# NRF8001_BLE_COMMS.net
KiCad netlist of a schematic drawn in EAGLE
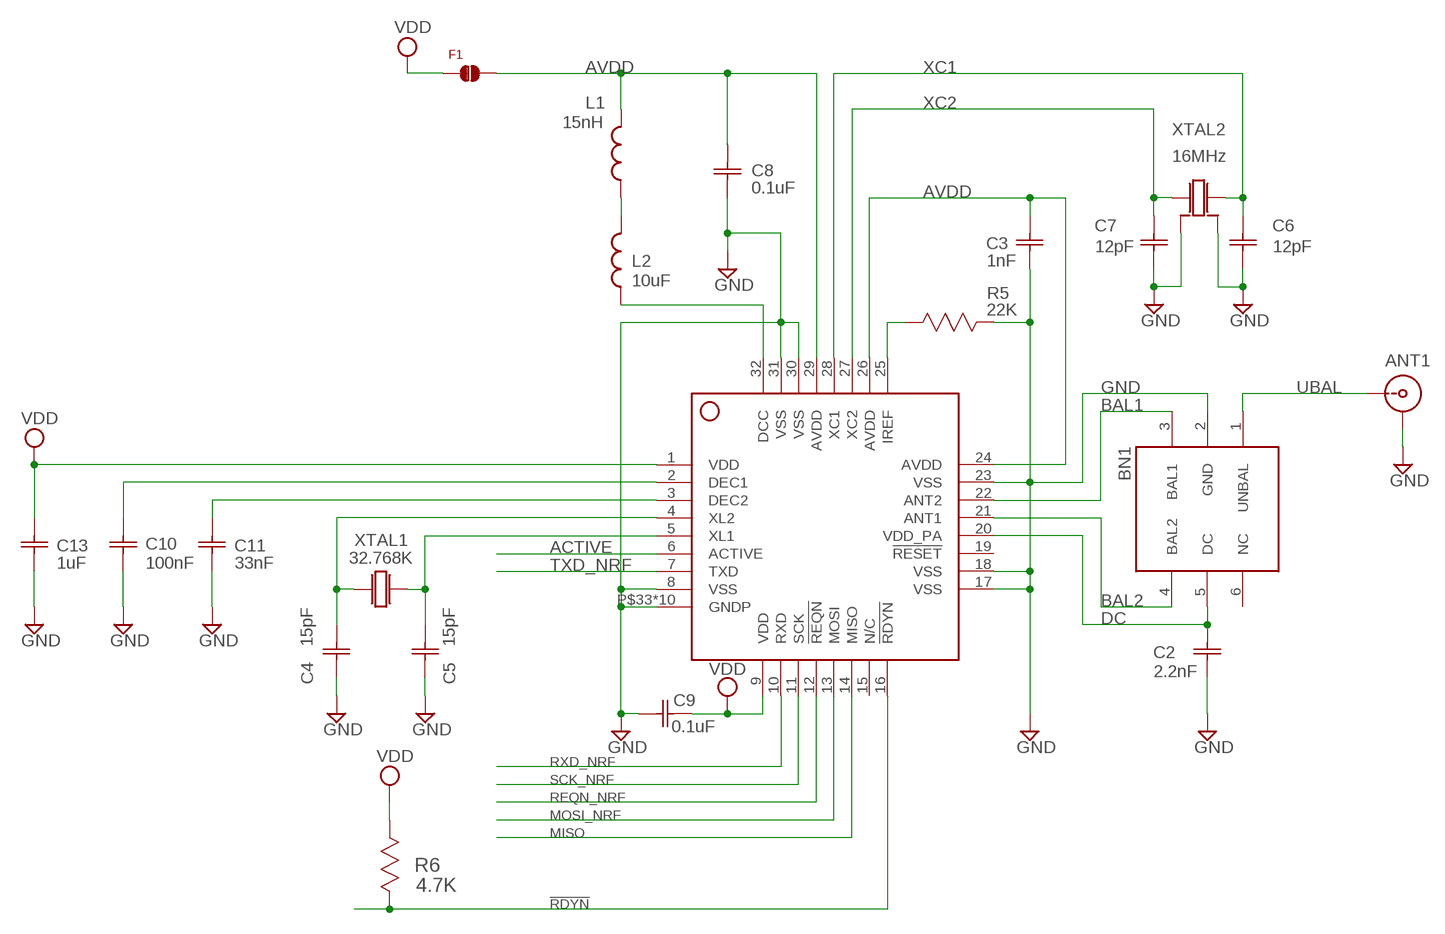
[diagram p0: schematic, sheet 1]

(export (version "E")
  (design (tool "Eeschema 10.0.6"))
  (components
    (comp (ref "ANT1")
      (value "U.FL-R-SMT(01)")
      (footprint "eagle-import:U.FL")
      (fields (field (name "MANUFACTURER") "HIROSE"))
      (libsource (lib "eagle-import") (part "U.FL-R-SMT(01)"))
    )
    (comp (ref "BN1")
      (value "2450BM14A0002")
      (footprint "eagle-import:BALUN")
      (fields (field (name "MANUFACTURER") "JOHANSON"))
      (libsource (lib "eagle-import") (part "2450BM14A0002"))
    )
    (comp (ref "C2")
      (value "2.2nF")
      (footprint "eagle-import:CAPC1608X85N")
      (fields (field (name "MPN") "C0603C222K5RACTU") (field (name "TOLERANCE") "±10%"))
      (libsource (lib "eagle-import") (part "C0603C222K5RACTU"))
    )
    (comp (ref "C3")
      (value "1nF")
      (footprint "eagle-import:CAPC1608X85N")
      (fields (field (name "MPN") "C0603C102J5GACTU") (field (name "TOLERANCE") "±5%"))
      (libsource (lib "eagle-import") (part "C0603C102J5GACTU"))
    )
    (comp (ref "C4")
      (value "15pF")
      (footprint "eagle-import:CAPC1608X85N")
      (fields (field (name "MPN") "C0603C150J5GACTU") (field (name "TOLERANCE") "±5%"))
      (libsource (lib "eagle-import") (part "C0603C150J5GACTU"))
    )
    (comp (ref "C5")
      (value "15pF")
      (footprint "eagle-import:CAPC1608X85N")
      (fields (field (name "MPN") "C0603C150J5GACTU") (field (name "TOLERANCE") "±5%"))
      (libsource (lib "eagle-import") (part "C0603C150J5GACTU"))
    )
    (comp (ref "C6")
      (value "12pF")
      (footprint "eagle-import:CAPC1608X85N")
      (fields (field (name "MPN") "C0603C120J5GACTU") (field (name "TOLERANCE") "±5%"))
      (libsource (lib "eagle-import") (part "C0603C120J5GACTU"))
    )
    (comp (ref "C7")
      (value "12pF")
      (footprint "eagle-import:CAPC1608X85N")
      (fields (field (name "MPN") "C0603C120J5GACTU") (field (name "TOLERANCE") "±5%"))
      (libsource (lib "eagle-import") (part "C0603C120J5GACTU"))
    )
    (comp (ref "C8")
      (value "0.1uF")
      (footprint "eagle-import:CAPC1608X90N")
      (fields (field (name "MPN") "0603YC104K4T4A") (field (name "TOLERANCE") "±10%"))
      (libsource (lib "eagle-import") (part "0603YC104K4T4A"))
    )
    (comp (ref "C9")
      (value "0.1uF")
      (footprint "eagle-import:CAPC1608X90N")
      (fields (field (name "MPN") "0603YC104K4T4A") (field (name "TOLERANCE") "±10%"))
      (libsource (lib "eagle-import") (part "0603YC104K4T4A"))
    )
    (comp (ref "C10")
      (value "100nF")
      (footprint "eagle-import:CAPC1608X90N")
      (fields (field (name "MPN") "06033C104JAT2A") (field (name "TOLERANCE") "±5%"))
      (libsource (lib "eagle-import") (part "06033C104JAT2A"))
    )
    (comp (ref "C11")
      (value "33nF")
      (footprint "eagle-import:CAPC1608X85N")
      (fields (field (name "MPN") "C0603C333K5RACTU") (field (name "TOLERANCE") "±10%"))
      (libsource (lib "eagle-import") (part "C0603C333K5RACTU"))
    )
    (comp (ref "C13")
      (value "1uF")
      (footprint "eagle-import:CAPC1608X90N")
      (fields (field (name "MPN") "0603YD105MAT4A") (field (name "TOLERANCE") "±20%"))
      (libsource (lib "eagle-import") (part "0603YD105MAT4A"))
    )
    (comp (ref "F1")
      (value "MMZ1608B121C")
      (footprint "eagle-import:0603")
      (libsource (lib "eagle-import") (part "MMZ1608B121C"))
    )
    (comp (ref "L1")
      (value "15nH")
      (footprint "eagle-import:0402")
      (libsource (lib "eagle-import") (part "HK100515NJ-T"))
    )
    (comp (ref "L2")
      (value "10uF")
      (footprint "eagle-import:0603")
      (libsource (lib "eagle-import") (part "LBMF1608T100K"))
    )
    (comp (ref "R5")
      (value "22K")
      (footprint "eagle-import:RESC1608X60N")
      (fields (field (name "MPN") "MC0.063W06031%22K") (field (name "TOLERANCE") "±1%"))
      (libsource (lib "eagle-import") (part "MC0.063W06031%22K"))
    )
    (comp (ref "R6")
      (value "4.7K")
      (footprint "eagle-import:RESC1608X60N")
      (fields (field (name "MPN") "MC0.063W06031%4K7") (field (name "TOLERANCE") "1%"))
      (libsource (lib "eagle-import") (part "MC0.063W06031%4K7"))
    )
    (comp (ref "U2")
      (value "NRF8001")
      (footprint "eagle-import:QFN50P500X500X90-33N")
      (fields (field (name "MANUFACTURER") "NORDIC SEMICONDUCTOR") (field (name "PARTNO") "nRF8001"))
      (libsource (lib "eagle-import") (part "NRF8001"))
    )
    (comp (ref "XTAL1")
      (value "32.768K")
      (footprint "eagle-import:3215")
      (libsource (lib "eagle-import") (part "NX3215SA-32.768K-STD-MUA-9"))
    )
    (comp (ref "XTAL2")
      (value "16MHz")
      (footprint "eagle-import:3225")
      (libsource (lib "eagle-import") (part "TSX-3225-16.0000MF18X-AC3"))
    )
  )
  (nets
    (net (code "1") (name "/ACTIVE") (class "Default")
      (node (ref "U2") (pin "6") (pinfunction "ACTIVE_6") (pintype "bidirectional"))
    )
    (net (code "2") (name "/AVDD") (class "Default")
      (node (ref "C3") (pin "2") (pinfunction "C2_2") (pintype "passive"))
      (node (ref "C8") (pin "2") (pinfunction "C2_2") (pintype "passive"))
      (node (ref "F1") (pin "P$2") (pinfunction "2_P$2") (pintype "bidirectional"))
      (node (ref "L1") (pin "P$2") (pinfunction "P$2_P$2") (pintype "bidirectional"))
      (node (ref "U2") (pin "24") (pinfunction "AVDD_24") (pintype "bidirectional"))
      (node (ref "U2") (pin "26") (pinfunction "AVDD_26") (pintype "bidirectional"))
      (node (ref "U2") (pin "29") (pinfunction "AVDD_29") (pintype "bidirectional"))
    )
    (net (code "3") (name "/BAL1") (class "Default")
      (node (ref "BN1") (pin "3") (pinfunction "BAL1_3") (pintype "bidirectional"))
      (node (ref "U2") (pin "22") (pinfunction "ANT2_22") (pintype "bidirectional"))
    )
    (net (code "4") (name "/BAL2") (class "Default")
      (node (ref "BN1") (pin "4") (pinfunction "BAL2_4") (pintype "bidirectional"))
      (node (ref "U2") (pin "21") (pinfunction "ANT1_21") (pintype "bidirectional"))
    )
    (net (code "5") (name "/DC") (class "Default")
      (node (ref "BN1") (pin "5") (pinfunction "DC_5") (pintype "bidirectional"))
      (node (ref "C2") (pin "2") (pinfunction "C2_2") (pintype "passive"))
      (node (ref "U2") (pin "20") (pinfunction "VDD_PA_20") (pintype "bidirectional"))
    )
    (net (code "6") (name "/MISO") (class "Default")
      (node (ref "U2") (pin "14") (pinfunction "MISO_14") (pintype "bidirectional"))
    )
    (net (code "7") (name "/MOSI_NRF") (class "Default")
      (node (ref "U2") (pin "13") (pinfunction "MOSI_13") (pintype "bidirectional"))
    )
    (net (code "8") (name "/REQN_NRF") (class "Default")
      (node (ref "U2") (pin "12") (pinfunction "~{REQN}_12") (pintype "bidirectional"))
    )
    (net (code "9") (name "/RXD_NRF") (class "Default")
      (node (ref "U2") (pin "10") (pinfunction "RXD_10") (pintype "bidirectional"))
    )
    (net (code "10") (name "/SCK_NRF") (class "Default")
      (node (ref "U2") (pin "11") (pinfunction "SCK_11") (pintype "bidirectional"))
    )
    (net (code "11") (name "/TXD_NRF") (class "Default")
      (node (ref "U2") (pin "7") (pinfunction "TXD_7") (pintype "bidirectional"))
    )
    (net (code "12") (name "/UBAL") (class "Default")
      (node (ref "ANT1") (pin "1") (pinfunction "P$1_1") (pintype "bidirectional"))
      (node (ref "BN1") (pin "1") (pinfunction "UNBAL_1") (pintype "bidirectional"))
    )
    (net (code "13") (name "/XC1") (class "Default")
      (node (ref "C6") (pin "2") (pinfunction "C2_2") (pintype "passive"))
      (node (ref "U2") (pin "28") (pinfunction "XC1_28") (pintype "bidirectional"))
      (node (ref "XTAL2") (pin "3") (pinfunction "3_3") (pintype "bidirectional"))
    )
    (net (code "14") (name "/XC2") (class "Default")
      (node (ref "C7") (pin "2") (pinfunction "C2_2") (pintype "passive"))
      (node (ref "U2") (pin "27") (pinfunction "XC2_27") (pintype "bidirectional"))
      (node (ref "XTAL2") (pin "1") (pinfunction "1_1") (pintype "bidirectional"))
    )
    (net (code "15") (name "/~{RDYN}") (class "Default")
      (node (ref "R6") (pin "2") (pinfunction "R2_2") (pintype "passive"))
      (node (ref "U2") (pin "16") (pinfunction "~{RDYN}_16") (pintype "bidirectional"))
    )
    (net (code "16") (name "GND") (class "Default")
      (node (ref "ANT1") (pin "2") (pinfunction "P$2_2") (pintype "bidirectional"))
      (node (ref "ANT1") (pin "3") (pinfunction "P$2_3") (pintype "bidirectional"))
      (node (ref "BN1") (pin "2") (pinfunction "GND_2") (pintype "bidirectional"))
      (node (ref "C10") (pin "1") (pinfunction "C1_1") (pintype "passive"))
      (node (ref "C11") (pin "2") (pinfunction "C2_2") (pintype "passive"))
      (node (ref "C13") (pin "1") (pinfunction "C1_1") (pintype "passive"))
      (node (ref "C2") (pin "1") (pinfunction "C1_1") (pintype "passive"))
      (node (ref "C3") (pin "1") (pinfunction "C1_1") (pintype "passive"))
      (node (ref "C4") (pin "1") (pinfunction "C1_1") (pintype "passive"))
      (node (ref "C5") (pin "1") (pinfunction "C1_1") (pintype "passive"))
      (node (ref "C6") (pin "1") (pinfunction "C1_1") (pintype "passive"))
      (node (ref "C7") (pin "1") (pinfunction "C1_1") (pintype "passive"))
      (node (ref "C8") (pin "1") (pinfunction "C1_1") (pintype "passive"))
      (node (ref "C9") (pin "2") (pinfunction "C2_2") (pintype "passive"))
      (node (ref "R5") (pin "1") (pinfunction "R1_1") (pintype "passive"))
      (node (ref "U2") (pin "17") (pinfunction "VSS_17") (pintype "bidirectional"))
      (node (ref "U2") (pin "18") (pinfunction "VSS_18") (pintype "bidirectional"))
      (node (ref "U2") (pin "23") (pinfunction "VSS_23") (pintype "bidirectional"))
      (node (ref "U2") (pin "30") (pinfunction "VSS_30") (pintype "bidirectional"))
      (node (ref "U2") (pin "31") (pinfunction "VSS_31") (pintype "bidirectional"))
      (node (ref "U2") (pin "8") (pinfunction "VSS_8") (pintype "bidirectional"))
      (node (ref "U2") (pin "P$33") (pinfunction "GNDP_P$33") (pintype "bidirectional"))
      (node (ref "U2") (pin "P$34") (pinfunction "GNDP_P$34") (pintype "bidirectional"))
      (node (ref "U2") (pin "P$35") (pinfunction "GNDP_P$35") (pintype "bidirectional"))
      (node (ref "U2") (pin "P$36") (pinfunction "GNDP_P$36") (pintype "bidirectional"))
      (node (ref "U2") (pin "P$37") (pinfunction "GNDP_P$37") (pintype "bidirectional"))
      (node (ref "U2") (pin "P$38") (pinfunction "GNDP_P$38") (pintype "bidirectional"))
      (node (ref "U2") (pin "P$39") (pinfunction "GNDP_P$39") (pintype "bidirectional"))
      (node (ref "U2") (pin "P$40") (pinfunction "GNDP_P$40") (pintype "bidirectional"))
      (node (ref "U2") (pin "P$41") (pinfunction "GNDP_P$41") (pintype "bidirectional"))
      (node (ref "U2") (pin "P$42") (pinfunction "GNDP_P$42") (pintype "bidirectional"))
      (node (ref "XTAL2") (pin "2") (pinfunction "2_2") (pintype "bidirectional"))
      (node (ref "XTAL2") (pin "4") (pinfunction "4_4") (pintype "bidirectional"))
    )
    (net (code "17") (name "Net-(C4-C2)") (class "Default")
      (node (ref "C4") (pin "2") (pinfunction "C2_2") (pintype "passive"))
      (node (ref "U2") (pin "4") (pinfunction "XL2_4") (pintype "bidirectional"))
      (node (ref "XTAL1") (pin "2") (pinfunction "2_2") (pintype "bidirectional"))
    )
    (net (code "18") (name "Net-(C5-C2)") (class "Default")
      (node (ref "C5") (pin "2") (pinfunction "C2_2") (pintype "passive"))
      (node (ref "U2") (pin "5") (pinfunction "XL1_5") (pintype "bidirectional"))
      (node (ref "XTAL1") (pin "1") (pinfunction "1_1") (pintype "bidirectional"))
    )
    (net (code "19") (name "Net-(C10-C2)") (class "Default")
      (node (ref "C10") (pin "2") (pinfunction "C2_2") (pintype "passive"))
      (node (ref "U2") (pin "2") (pinfunction "DEC1_2") (pintype "bidirectional"))
    )
    (net (code "20") (name "Net-(C11-C1)") (class "Default")
      (node (ref "C11") (pin "1") (pinfunction "C1_1") (pintype "passive"))
      (node (ref "U2") (pin "3") (pinfunction "DEC2_3") (pintype "bidirectional"))
    )
    (net (code "21") (name "Net-(L1-PadP$1)") (class "Default")
      (node (ref "L1") (pin "P$1") (pinfunction "P$1_P$1") (pintype "bidirectional"))
      (node (ref "L2") (pin "2") (pinfunction "2_2") (pintype "bidirectional"))
    )
    (net (code "22") (name "Net-(R5-R2)") (class "Default")
      (node (ref "R5") (pin "2") (pinfunction "R2_2") (pintype "passive"))
      (node (ref "U2") (pin "25") (pinfunction "IREF_25") (pintype "bidirectional"))
    )
    (net (code "23") (name "Net-(U2-DCC)") (class "Default")
      (node (ref "L2") (pin "1") (pinfunction "1_1") (pintype "bidirectional"))
      (node (ref "U2") (pin "32") (pinfunction "DCC_32") (pintype "bidirectional"))
    )
    (net (code "24") (name "VDD") (class "Default")
      (node (ref "C13") (pin "2") (pinfunction "C2_2") (pintype "passive"))
      (node (ref "C9") (pin "1") (pinfunction "C1_1") (pintype "passive"))
      (node (ref "F1") (pin "P$1") (pinfunction "1_P$1") (pintype "bidirectional"))
      (node (ref "R6") (pin "1") (pinfunction "R1_1") (pintype "passive"))
      (node (ref "U2") (pin "1") (pinfunction "VDD_1") (pintype "bidirectional"))
      (node (ref "U2") (pin "9") (pinfunction "VDD_9") (pintype "bidirectional"))
    )
    (net (code "25") (name "unconnected-(BN1-NC-Pad6)") (class "Default")
      (node (ref "BN1") (pin "6") (pinfunction "NC_6") (pintype "bidirectional"))
    )
    (net (code "26") (name "unconnected-(U2-N{slash}C-Pad15)") (class "Default")
      (node (ref "U2") (pin "15") (pinfunction "N/C_15") (pintype "bidirectional"))
    )
    (net (code "27") (name "unconnected-(U2-~{RESET}-Pad19)") (class "Default")
      (node (ref "U2") (pin "19") (pinfunction "~{RESET}_19") (pintype "bidirectional"))
    )
  )
)
